# tekprobe.net
KiCad netlist of a schematic drawn in Altium Designer
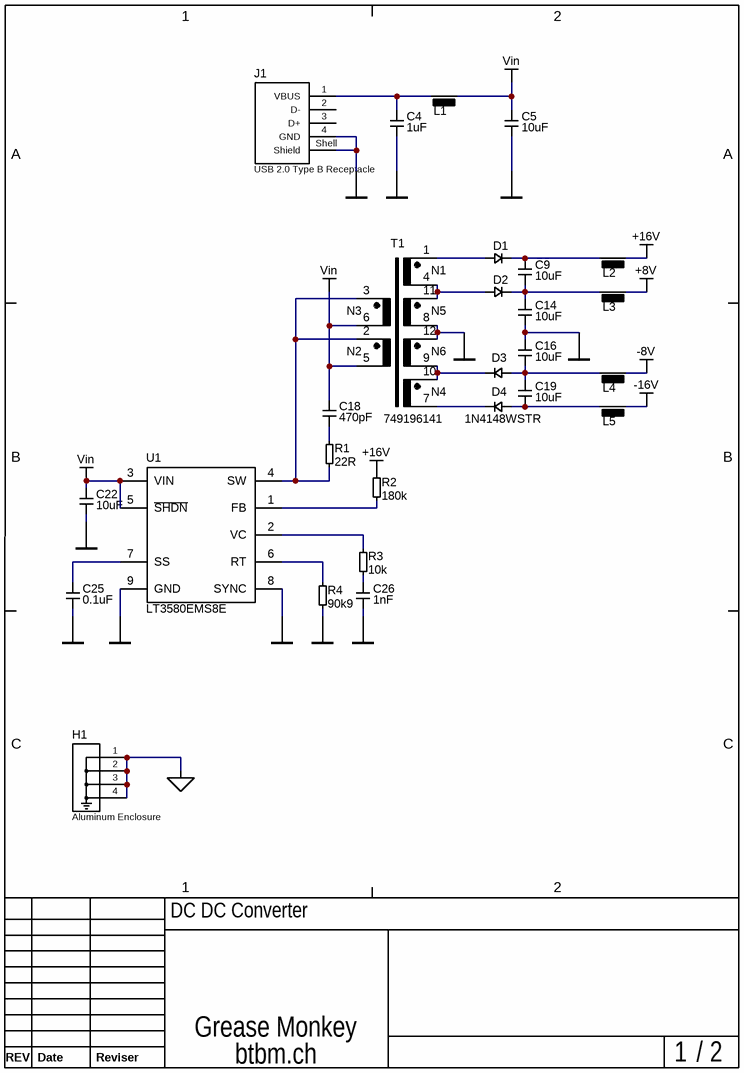
[diagram p0: tekprobe.SchDoc]

(export (version "E")
  (design (tool "Eeschema 10.0.6"))
  (components
    (comp (ref "C4")
      (value "1uF")
      (footprint "CAP_0805")
      (description "CAP CER 1UF 25V X7R 0805")
      (fields
        (field (name "MANUFACTURER") "Samsung")
        (field (name "MANUFACTURER PART NUMBER") "CL21B105KAFNFNE")
      )
      (libsource (lib "*") (part "CL21B105KAFNFNE"))
    )
    (comp (ref "C5")
      (value "10uF")
      (footprint "CAP_0805")
      (description "CAP CER 10UF 25V X5R 0805")
      (fields
        (field (name "MANUFACTURER") "Samsung")
        (field (name "MANUFACTURER PART NUMBER") "CL21A106KAYNNNG")
      )
      (libsource (lib "tekprobe") (part "CL21A106KAYNNNG"))
    )
    (comp (ref "C9")
      (value "10uF")
      (footprint "CAP_0805")
      (description "CAP CER 10UF 25V X5R 0805")
      (fields
        (field (name "MANUFACTURER") "Samsung")
        (field (name "MANUFACTURER PART NUMBER") "CL21A106KAYNNNG")
      )
      (libsource (lib "tekprobe") (part "CL21A106KAYNNNG"))
    )
    (comp (ref "C14")
      (value "10uF")
      (footprint "CAP_0805")
      (description "CAP CER 10UF 25V X5R 0805")
      (fields
        (field (name "MANUFACTURER") "Samsung")
        (field (name "MANUFACTURER PART NUMBER") "CL21A106KAYNNNG")
      )
      (libsource (lib "tekprobe") (part "CL21A106KAYNNNG"))
    )
    (comp (ref "C16")
      (value "10uF")
      (footprint "CAP_0805")
      (description "CAP CER 10UF 25V X5R 0805")
      (fields
        (field (name "MANUFACTURER") "Samsung")
        (field (name "MANUFACTURER PART NUMBER") "CL21A106KAYNNNG")
      )
      (libsource (lib "tekprobe") (part "CL21A106KAYNNNG"))
    )
    (comp (ref "C18")
      (value "470pF")
      (footprint "CAP_0805")
      (description "CAP CER 470PF 50V X7R 0805")
      (fields
        (field (name "MANUFACTURER") "Wurth Electronics")
        (field (name "MANUFACTURER PART NUMBER") "885012207084")
      )
      (libsource (lib "tekprobe") (part "885012207084"))
    )
    (comp (ref "C19")
      (value "10uF")
      (footprint "CAP_0805")
      (description "CAP CER 10UF 25V X5R 0805")
      (fields
        (field (name "MANUFACTURER") "Samsung")
        (field (name "MANUFACTURER PART NUMBER") "CL21A106KAYNNNG")
      )
      (libsource (lib "tekprobe") (part "CL21A106KAYNNNG"))
    )
    (comp (ref "C22")
      (value "10uF")
      (footprint "CAP_0805")
      (description "CAP CER 10UF 25V X5R 0805")
      (fields
        (field (name "MANUFACTURER") "Samsung")
        (field (name "MANUFACTURER PART NUMBER") "CL21A106KAYNNNG")
      )
      (libsource (lib "tekprobe") (part "CL21A106KAYNNNG"))
    )
    (comp (ref "C25")
      (value "0.1uF")
      (footprint "CAP_0805")
      (description "CAP CER 0.1UF 25V X7R 0805")
      (fields
        (field (name "MANUFACTURER") "Samsung")
        (field (name "MANUFACTURER PART NUMBER") "CL21B104MACNNNC")
      )
      (libsource (lib "tekprobe") (part "CL21B104MACNNNC"))
    )
    (comp (ref "C26")
      (value "1nF")
      (footprint "CAP_0805")
      (description "Cap Ceramic 0.001uF 50VDC X7R 10% SMD 0805 Paper T/R")
      (fields
        (field (name "MANUFACTURER") "Samsung")
        (field (name "MANUFACTURER PART NUMBER") "CL21B102KBANNNC")
      )
      (libsource (lib "tekprobe") (part "CL21B102KBANNNC"))
    )
    (comp (ref "D1")
      (value "1N4148WSTR")
      (footprint "SODFL250X100-2N")
      (description "DIODE GEN PURP 75V 300MA SOD323")
      (fields (field (name "MANUFACTURER") "SMC"))
      (libsource (lib "tekprobe") (part "1N4148WSTR"))
    )
    (comp (ref "D2")
      (value "1N4148WSTR")
      (footprint "SODFL250X100-2N")
      (description "DIODE GEN PURP 75V 300MA SOD323")
      (fields (field (name "MANUFACTURER") "SMC"))
      (libsource (lib "tekprobe") (part "1N4148WSTR"))
    )
    (comp (ref "D3")
      (value "1N4148WSTR")
      (footprint "SODFL250X100-2N")
      (description "DIODE GEN PURP 75V 300MA SOD323")
      (fields (field (name "MANUFACTURER") "SMC"))
      (libsource (lib "tekprobe") (part "1N4148WSTR"))
    )
    (comp (ref "D4")
      (value "1N4148WSTR")
      (footprint "SODFL250X100-2N")
      (description "DIODE GEN PURP 75V 300MA SOD323")
      (fields (field (name "MANUFACTURER") "SMC"))
      (libsource (lib "tekprobe") (part "1N4148WSTR"))
    )
    (comp (ref "H1")
      (value "Aluminum Enclosure")
      (footprint "1550Q")
      (description "BOX ALUM UNPAINTED 2.36\"LX2.17\"W")
      (fields
        (field (name "MANUFACTURER") "Hammond Manufacturing")
        (field (name "MANUFACTURER PART NUMBER") "1550Q")
      )
      (libsource (lib "tekprobe") (part "1550Q"))
    )
    (comp (ref "J1")
      (value "USB 2.0 Type B Receptacle")
      (footprint "61400413321")
      (description "USB 2.0 Type B, Receptacle, Vertical, THT")
      (fields
        (field (name "MANUFACTURER") "Wurth Elektronik")
        (field (name "MANUFACTURER PART NUMBER") "61400413321")
      )
      (libsource (lib "tekprobe") (part "61400413321"))
    )
    (comp (ref "L1")
      (value "Ferrite Bead")
      (footprint "RES_0805")
      (description "Ferrite Chip Bead 800Ohm 800mA 0.3Ohm Multi-Layer 2-Pin 0805 T/R")
      (fields
        (field (name "MANUFACTURER") "Cooper Bussmann")
        (field (name "MANUFACTURER PART NUMBER") "MFBW1V2012-801-R")
      )
      (libsource (lib "tekprobe") (part "MFBW1V2012-801-R"))
    )
    (comp (ref "L2")
      (value "Ferrite Bead")
      (footprint "RES_0805")
      (description "Ferrite Chip Bead 800Ohm 800mA 0.3Ohm Multi-Layer 2-Pin 0805 T/R")
      (fields
        (field (name "MANUFACTURER") "Cooper Bussmann")
        (field (name "MANUFACTURER PART NUMBER") "MFBW1V2012-801-R")
      )
      (libsource (lib "tekprobe") (part "MFBW1V2012-801-R"))
    )
    (comp (ref "L3")
      (value "Ferrite Bead")
      (footprint "RES_0805")
      (description "Ferrite Chip Bead 800Ohm 800mA 0.3Ohm Multi-Layer 2-Pin 0805 T/R")
      (fields
        (field (name "MANUFACTURER") "Cooper Bussmann")
        (field (name "MANUFACTURER PART NUMBER") "MFBW1V2012-801-R")
      )
      (libsource (lib "tekprobe") (part "MFBW1V2012-801-R"))
    )
    (comp (ref "L4")
      (value "Ferrite Bead")
      (footprint "RES_0805")
      (description "Ferrite Chip Bead 800Ohm 800mA 0.3Ohm Multi-Layer 2-Pin 0805 T/R")
      (fields
        (field (name "MANUFACTURER") "Cooper Bussmann")
        (field (name "MANUFACTURER PART NUMBER") "MFBW1V2012-801-R")
      )
      (libsource (lib "tekprobe") (part "MFBW1V2012-801-R"))
    )
    (comp (ref "L5")
      (value "Ferrite Bead")
      (footprint "RES_0805")
      (description "Ferrite Chip Bead 800Ohm 800mA 0.3Ohm Multi-Layer 2-Pin 0805 T/R")
      (fields
        (field (name "MANUFACTURER") "Cooper Bussmann")
        (field (name "MANUFACTURER PART NUMBER") "MFBW1V2012-801-R")
      )
      (libsource (lib "tekprobe") (part "MFBW1V2012-801-R"))
    )
    (comp (ref "R1")
      (value "22R")
      (footprint "RES_0805")
      (description "RES 22 OHM 1/8W 1% 0805 SMD")
      (fields
        (field (name "MANUFACTURER") "Stackpole Electronics")
        (field (name "MANUFACTURER PART NUMBER") "RMCF0805FT22R0")
      )
      (libsource (lib "tekprobe") (part "RMCF0805FT22R0"))
    )
    (comp (ref "R2")
      (value "180k")
      (footprint "RES_0805")
      (description "Thick Film Resistors 1/4W 180K OHM 1%")
      (fields
        (field (name "MANUFACTURER") "KOA Speer")
        (field (name "MANUFACTURER PART NUMBER") "RK73H2ATTD1803F")
      )
      (libsource (lib "tekprobe") (part "RK73H2ATTD1803F"))
    )
    (comp (ref "R3")
      (value "10k")
      (footprint "RES_0805")
      (description "RES 10K OHM 1% 1/8W 0805")
      (fields
        (field (name "MANUFACTURER") "Stackpole Electronics")
        (field (name "MANUFACTURER PART NUMBER") "RMCF0805FT10K0")
      )
      (libsource (lib "tekprobe") (part "RMCF0805FT10K0"))
    )
    (comp (ref "R4")
      (value "90k9")
      (footprint "RES_0805")
      (description "Res Thick Film 0805 90.9K Ohm 1% 0.125W ±100ppm/°C Molded SMD Paper T/R")
      (fields
        (field (name "MANUFACTURER") "Stackpole Electronics")
        (field (name "MANUFACTURER PART NUMBER") "RMCF0805FT90K9")
      )
      (libsource (lib "tekprobe") (part "RMCF0805FT90K9"))
    )
    (comp (ref "T1")
      (value "Transformer")
      (footprint "WE-FLEX_ER11/5")
      (description "Flex Transformer WE-FLEX ER11/5")
      (fields
        (field (name "MANUFACTURER") "Wurth Electronics")
        (field (name "MANUFACTURER PART NUMBER") "749196141")
      )
      (libsource (lib "tekprobe") (part "Transformer_749196141"))
    )
    (comp (ref "U1")
      (value "LT3580EMS8E")
      (footprint "LT3580")
      (description "IC REG MULT CONFIG INV ADJ 8MSOP")
      (fields
        (field (name "MANUFACTURER") "Analog Devices / Linear Technology")
        (field (name "MANUFACTURER PART NUMBER") "LT3580EMS8E#PBF")
      )
      (libsource (lib "tekprobe") (part "LT3580EMS8E"))
    )
  )
  (nets
    (net (code "1") (name "+8V") (class "Default")
      (node (ref "L3") (pin "2") (pinfunction "2_2") (pintype "passive"))
    )
    (net (code "2") (name "+16V") (class "Default")
      (node (ref "L2") (pin "2") (pinfunction "2_2") (pintype "passive"))
      (node (ref "R2") (pin "1") (pinfunction "1_1") (pintype "passive"))
    )
    (net (code "3") (name "-8V") (class "Default")
      (node (ref "L4") (pin "2") (pinfunction "2_2") (pintype "passive"))
    )
    (net (code "4") (name "-16V") (class "Default")
      (node (ref "L5") (pin "2") (pinfunction "2_2") (pintype "passive"))
    )
    (net (code "5") (name "0V") (class "Default")
      (node (ref "C14") (pin "2") (pinfunction "2_2") (pintype "passive"))
      (node (ref "C16") (pin "1") (pinfunction "1_1") (pintype "passive"))
      (node (ref "C22") (pin "2") (pinfunction "2_2") (pintype "passive"))
      (node (ref "C25") (pin "2") (pinfunction "2_2") (pintype "passive"))
      (node (ref "C26") (pin "2") (pinfunction "2_2") (pintype "passive"))
      (node (ref "C4") (pin "2") (pinfunction "2_2") (pintype "passive"))
      (node (ref "C5") (pin "2") (pinfunction "2_2") (pintype "passive"))
      (node (ref "H1") (pin "1") (pinfunction "DATA_1") (pintype "passive"))
      (node (ref "H1") (pin "2") (pinfunction "-15V_2") (pintype "passive"))
      (node (ref "H1") (pin "3") (pinfunction "-5V_3") (pintype "passive"))
      (node (ref "H1") (pin "4") (pinfunction "OFFSET_4") (pintype "passive"))
      (node (ref "J1") (pin "4") (pinfunction "GND_4") (pintype "passive"))
      (node (ref "J1") (pin "Shell") (pinfunction "Shield_Shell") (pintype "passive"))
      (node (ref "R4") (pin "2") (pinfunction "2_2") (pintype "passive"))
      (node (ref "T1") (pin "12") (pinfunction "N6dot_12") (pintype "passive"))
      (node (ref "T1") (pin "8") (pinfunction "N5_8") (pintype "passive"))
      (node (ref "U1") (pin "8") (pinfunction "SYNC_8") (pintype "passive"))
      (node (ref "U1") (pin "9") (pinfunction "GND_9") (pintype "passive"))
    )
    (net (code "6") (name "Net-(C9-Pad1)") (class "Default")
      (node (ref "C9") (pin "1") (pinfunction "1_1") (pintype "passive"))
      (node (ref "D1") (pin "K") (pinfunction "K_K") (pintype "passive"))
      (node (ref "L2") (pin "1") (pinfunction "1_1") (pintype "passive"))
    )
    (net (code "7") (name "Net-(C14-Pad1)") (class "Default")
      (node (ref "C14") (pin "1") (pinfunction "1_1") (pintype "passive"))
      (node (ref "C9") (pin "2") (pinfunction "2_2") (pintype "passive"))
      (node (ref "D2") (pin "K") (pinfunction "K_K") (pintype "passive"))
      (node (ref "L3") (pin "1") (pinfunction "1_1") (pintype "passive"))
    )
    (net (code "8") (name "Net-(C16-Pad2)") (class "Default")
      (node (ref "C16") (pin "2") (pinfunction "2_2") (pintype "passive"))
      (node (ref "C19") (pin "1") (pinfunction "1_1") (pintype "passive"))
      (node (ref "D3") (pin "A") (pinfunction "A_A") (pintype "passive"))
      (node (ref "L4") (pin "1") (pinfunction "1_1") (pintype "passive"))
    )
    (net (code "9") (name "Net-(C18-Pad2)") (class "Default")
      (node (ref "C18") (pin "2") (pinfunction "2_2") (pintype "passive"))
      (node (ref "R1") (pin "1") (pinfunction "1_1") (pintype "passive"))
    )
    (net (code "10") (name "Net-(C19-Pad2)") (class "Default")
      (node (ref "C19") (pin "2") (pinfunction "2_2") (pintype "passive"))
      (node (ref "D4") (pin "A") (pinfunction "A_A") (pintype "passive"))
      (node (ref "L5") (pin "1") (pinfunction "1_1") (pintype "passive"))
    )
    (net (code "11") (name "Net-(C26-Pad1)") (class "Default")
      (node (ref "C26") (pin "1") (pinfunction "1_1") (pintype "passive"))
      (node (ref "R3") (pin "2") (pinfunction "2_2") (pintype "passive"))
    )
    (net (code "12") (name "Net-(J1-VBUS)") (class "Default")
      (node (ref "C4") (pin "1") (pinfunction "1_1") (pintype "passive"))
      (node (ref "J1") (pin "1") (pinfunction "VBUS_1") (pintype "passive"))
      (node (ref "L1") (pin "1") (pinfunction "1_1") (pintype "passive"))
    )
    (net (code "13") (name "Net-(T1-N1)") (class "Default")
      (node (ref "D2") (pin "A") (pinfunction "A_A") (pintype "passive"))
      (node (ref "T1") (pin "11") (pinfunction "N5dot_11") (pintype "passive"))
      (node (ref "T1") (pin "4") (pinfunction "N1_4") (pintype "passive"))
    )
    (net (code "14") (name "Net-(T1-N1dot)") (class "Default")
      (node (ref "D1") (pin "A") (pinfunction "A_A") (pintype "passive"))
      (node (ref "T1") (pin "1") (pinfunction "N1dot_1") (pintype "passive"))
    )
    (net (code "15") (name "Net-(T1-N2dot)") (class "Default")
      (node (ref "R1") (pin "2") (pinfunction "2_2") (pintype "passive"))
      (node (ref "T1") (pin "2") (pinfunction "N2dot_2") (pintype "passive"))
      (node (ref "T1") (pin "3") (pinfunction "N3dot_3") (pintype "passive"))
      (node (ref "U1") (pin "4") (pinfunction "SW_4") (pintype "passive"))
    )
    (net (code "16") (name "Net-(T1-N4)") (class "Default")
      (node (ref "D4") (pin "K") (pinfunction "K_K") (pintype "passive"))
      (node (ref "T1") (pin "7") (pinfunction "N4_7") (pintype "passive"))
    )
    (net (code "17") (name "Net-(T1-N4dot)") (class "Default")
      (node (ref "D3") (pin "K") (pinfunction "K_K") (pintype "passive"))
      (node (ref "T1") (pin "10") (pinfunction "N4dot_10") (pintype "passive"))
      (node (ref "T1") (pin "9") (pinfunction "N6_9") (pintype "passive"))
    )
    (net (code "18") (name "Net-(U1-FB)") (class "Default")
      (node (ref "R2") (pin "2") (pinfunction "2_2") (pintype "passive"))
      (node (ref "U1") (pin "1") (pinfunction "FB_1") (pintype "passive"))
    )
    (net (code "19") (name "Net-(U1-RT)") (class "Default")
      (node (ref "R4") (pin "1") (pinfunction "1_1") (pintype "passive"))
      (node (ref "U1") (pin "6") (pinfunction "RT_6") (pintype "passive"))
    )
    (net (code "20") (name "Net-(U1-SS)") (class "Default")
      (node (ref "C25") (pin "1") (pinfunction "1_1") (pintype "passive"))
      (node (ref "U1") (pin "7") (pinfunction "SS_7") (pintype "passive"))
    )
    (net (code "21") (name "Net-(U1-VC)") (class "Default")
      (node (ref "R3") (pin "1") (pinfunction "1_1") (pintype "passive"))
      (node (ref "U1") (pin "2") (pinfunction "VC_2") (pintype "passive"))
    )
    (net (code "22") (name "Vin") (class "Default")
      (node (ref "C18") (pin "1") (pinfunction "1_1") (pintype "passive"))
      (node (ref "C22") (pin "1") (pinfunction "1_1") (pintype "passive"))
      (node (ref "C5") (pin "1") (pinfunction "1_1") (pintype "passive"))
      (node (ref "L1") (pin "2") (pinfunction "2_2") (pintype "passive"))
      (node (ref "T1") (pin "5") (pinfunction "N2_5") (pintype "passive"))
      (node (ref "T1") (pin "6") (pinfunction "N3_6") (pintype "passive"))
      (node (ref "U1") (pin "3") (pinfunction "VIN_3") (pintype "passive"))
      (node (ref "U1") (pin "5") (pinfunction "~{SHDN}_5") (pintype "passive"))
    )
    (net (code "23") (name "unconnected-(J1-D+-Pad3)") (class "Default")
      (node (ref "J1") (pin "3") (pinfunction "D+_3") (pintype "passive"))
    )
    (net (code "24") (name "unconnected-(J1-D--Pad2)") (class "Default")
      (node (ref "J1") (pin "2") (pinfunction "D-_2") (pintype "passive"))
    )
  )
)
